# DBG-001.net
KiCad netlist of a schematic drawn in EAGLE
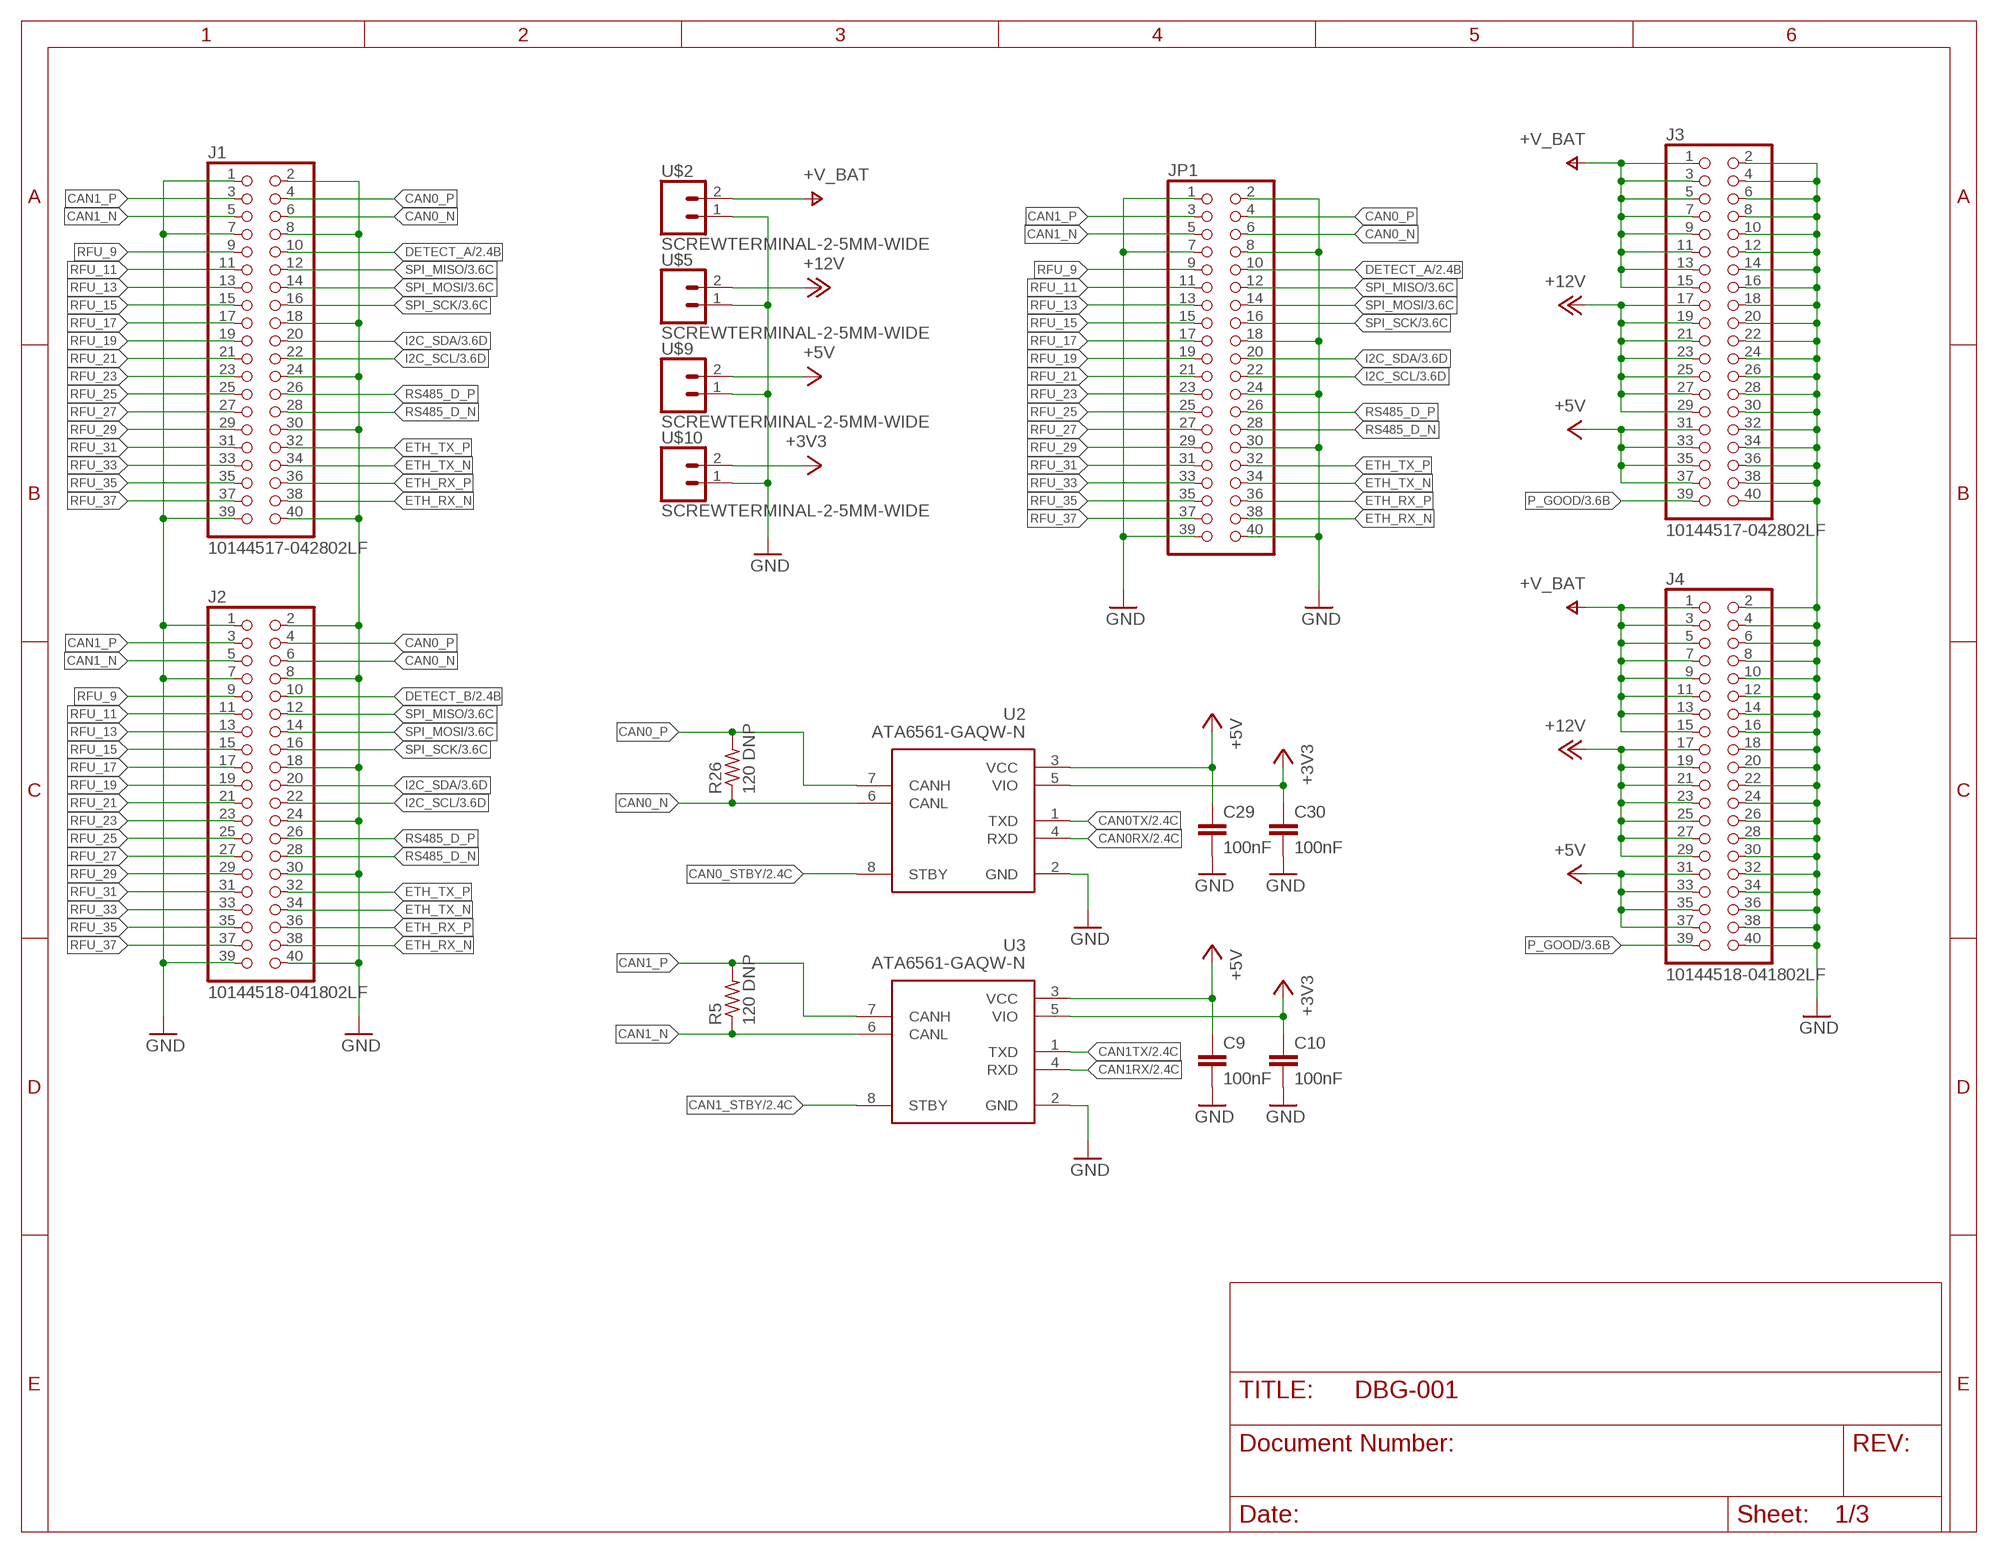
[diagram p0: schematic, sheet 1]
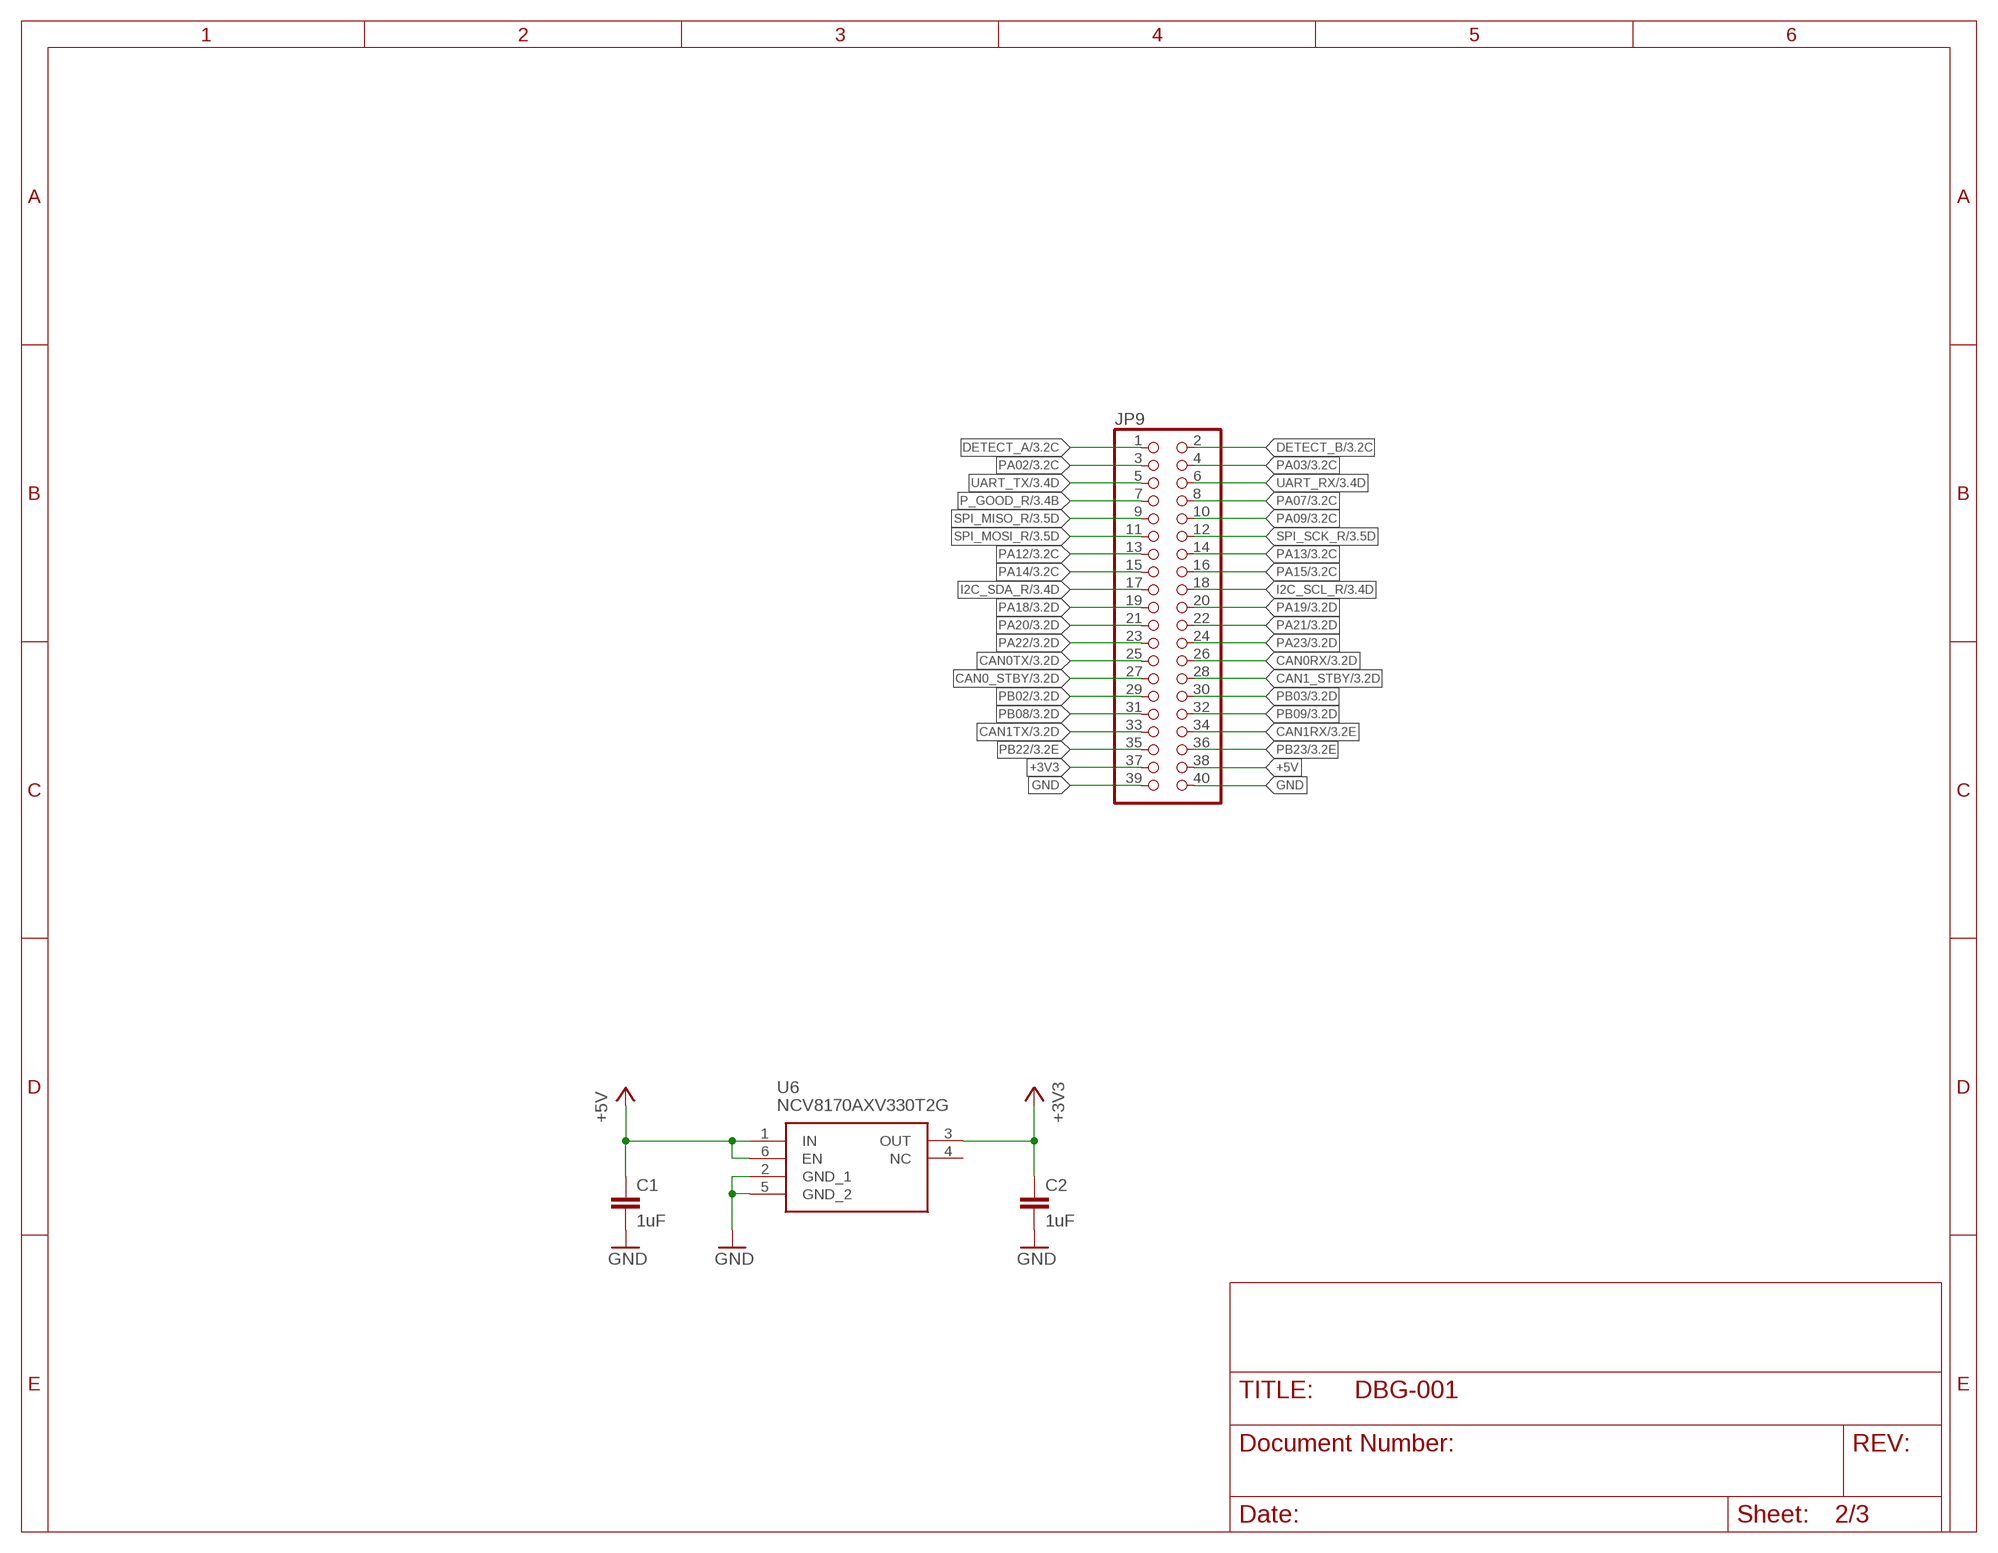
[diagram p1: schematic, sheet 2]
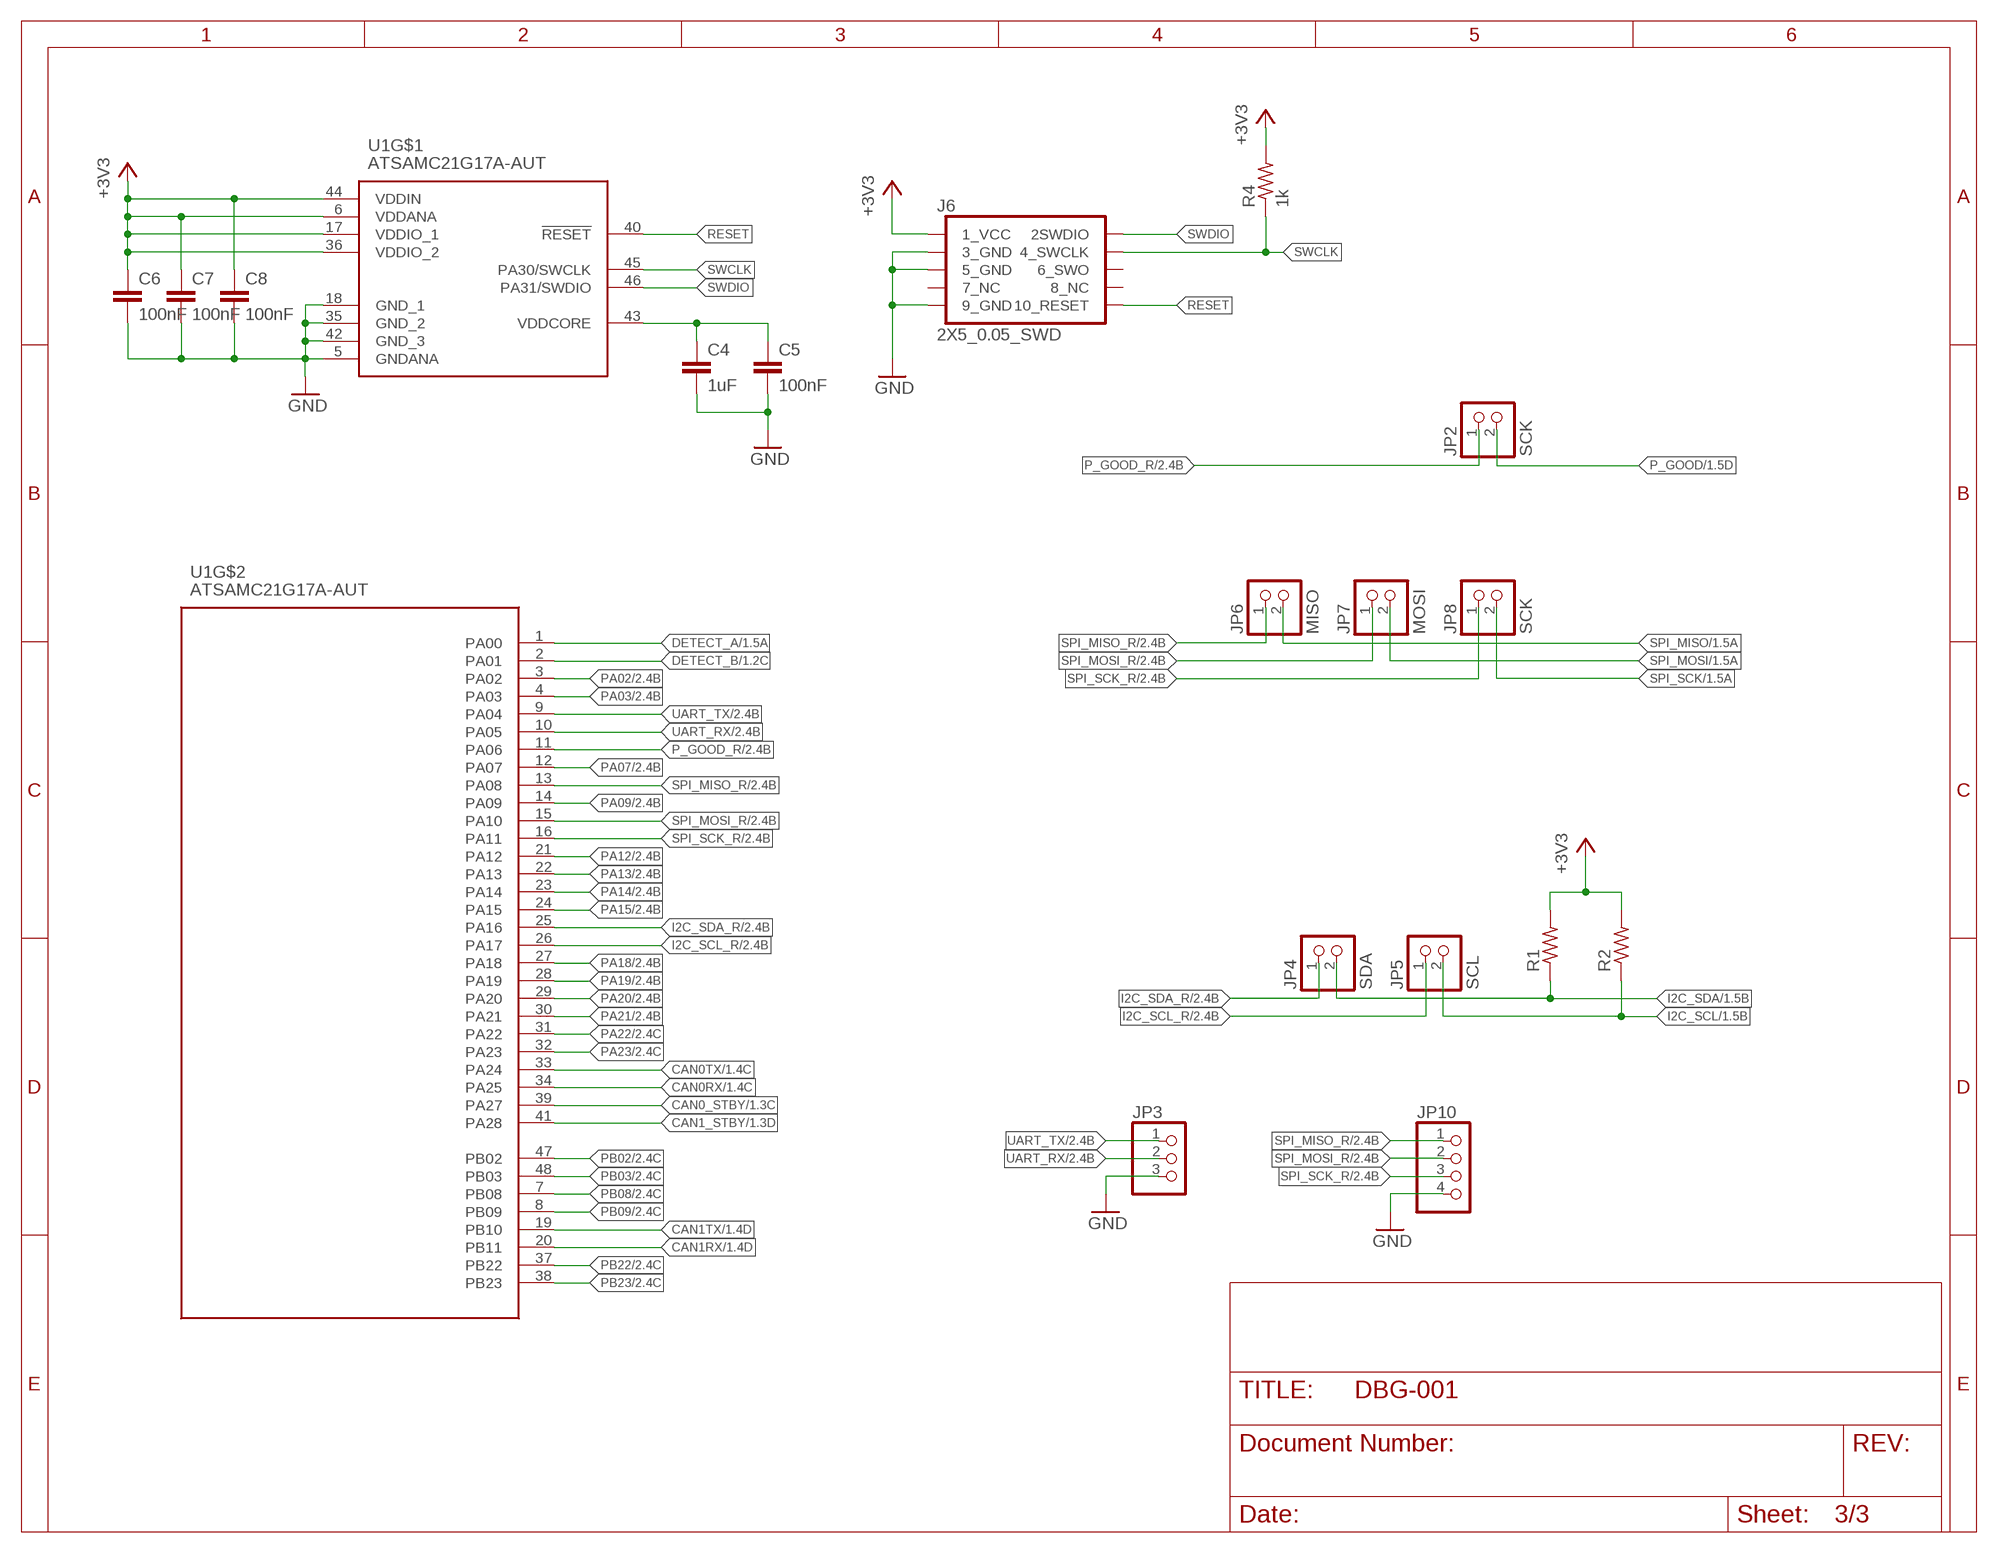
[diagram p2: schematic, sheet 3]

(export (version "E")
  (design (tool "Eeschema 10.0.6"))
  (components
    (comp (ref "C1")
      (value "1uF")
      (footprint "eagle-import:C0603")
      (libsource (lib "eagle-import") (part "C-EUC0603"))
    )
    (comp (ref "C2")
      (value "1uF")
      (footprint "eagle-import:C0603")
      (libsource (lib "eagle-import") (part "C-EUC0603"))
    )
    (comp (ref "JP9")
      (value "PINHD-2X20")
      (footprint "eagle-import:2X20")
      (libsource (lib "eagle-import") (part "PINHD-2X20"))
    )
    (comp (ref "U6")
      (value "NCV8170AXV330T2G")
      (footprint "eagle-import:SOTFL50P160X60-6N")
      (fields (field (name "MOUSER_PART_NUMBER") "863-NCV8170AXV330T2G"))
      (libsource (lib "eagle-import") (part "NCV8170AXV330T2G"))
    )
    (comp (ref "C9")
      (value "100nF")
      (footprint "eagle-import:C0402")
      (libsource (lib "eagle-import") (part "C-EUC0402"))
    )
    (comp (ref "C10")
      (value "100nF")
      (footprint "eagle-import:C0402")
      (libsource (lib "eagle-import") (part "C-EUC0402"))
    )
    (comp (ref "C29")
      (value "100nF")
      (footprint "eagle-import:C0402")
      (libsource (lib "eagle-import") (part "C-EUC0402"))
    )
    (comp (ref "C30")
      (value "100nF")
      (footprint "eagle-import:C0402")
      (libsource (lib "eagle-import") (part "C-EUC0402"))
    )
    (comp (ref "J1")
      (value "10144517-042802LF")
      (footprint "eagle-import:10144517-042802LF")
      (libsource (lib "eagle-import") (part "10144517-042802LF"))
    )
    (comp (ref "J2")
      (value "10144518-041802LF")
      (footprint "eagle-import:10144518-041802LF")
      (libsource (lib "eagle-import") (part "10144518-041802LF"))
    )
    (comp (ref "J3")
      (value "10144517-042802LF")
      (footprint "eagle-import:10144517-042802LF")
      (libsource (lib "eagle-import") (part "10144517-042802LF"))
    )
    (comp (ref "J4")
      (value "10144518-041802LF")
      (footprint "eagle-import:10144518-041802LF")
      (libsource (lib "eagle-import") (part "10144518-041802LF"))
    )
    (comp (ref "JP1")
      (value "PINHD-2X20")
      (footprint "eagle-import:2X20")
      (libsource (lib "eagle-import") (part "PINHD-2X20"))
    )
    (comp (ref "R5")
      (value "120 DNP")
      (footprint "eagle-import:R0402")
      (libsource (lib "eagle-import") (part "R-US_R0402"))
    )
    (comp (ref "R26")
      (value "120 DNP")
      (footprint "eagle-import:R0402")
      (libsource (lib "eagle-import") (part "R-US_R0402"))
    )
    (comp (ref "U$2")
      (value "SCREWTERMINAL-2-5MM-WIDE")
      (footprint "eagle-import:SCREWTERMINAL-5MM-2-WIDE")
      (libsource (lib "eagle-import") (part "SCREWTERMINAL-2-5MM-WIDE"))
    )
    (comp (ref "U$5")
      (value "SCREWTERMINAL-2-5MM-WIDE")
      (footprint "eagle-import:SCREWTERMINAL-5MM-2-WIDE")
      (libsource (lib "eagle-import") (part "SCREWTERMINAL-2-5MM-WIDE"))
    )
    (comp (ref "U$9")
      (value "SCREWTERMINAL-2-5MM-WIDE")
      (footprint "eagle-import:SCREWTERMINAL-5MM-2-WIDE")
      (libsource (lib "eagle-import") (part "SCREWTERMINAL-2-5MM-WIDE"))
    )
    (comp (ref "U$10")
      (value "SCREWTERMINAL-2-5MM-WIDE")
      (footprint "eagle-import:SCREWTERMINAL-5MM-2-WIDE")
      (libsource (lib "eagle-import") (part "SCREWTERMINAL-2-5MM-WIDE"))
    )
    (comp (ref "U2")
      (value "ATA6561-GAQW-N")
      (footprint "eagle-import:SOIC127P600X175-8N")
      (fields (field (name "MOUSER_PART_NUMBER") "579-ATA6561-GAQW-N"))
      (libsource (lib "eagle-import") (part "ATA6561-GAQW-N"))
    )
    (comp (ref "U3")
      (value "ATA6561-GAQW-N")
      (footprint "eagle-import:SOIC127P600X175-8N")
      (fields (field (name "MOUSER_PART_NUMBER") "579-ATA6561-GAQW-N"))
      (libsource (lib "eagle-import") (part "ATA6561-GAQW-N"))
    )
    (comp (ref "C4")
      (value "1uF")
      (footprint "eagle-import:C0805")
      (libsource (lib "eagle-import") (part "C-EUC0805"))
    )
    (comp (ref "C5")
      (value "100nF")
      (footprint "eagle-import:C0805")
      (libsource (lib "eagle-import") (part "C-EUC0805"))
    )
    (comp (ref "C6")
      (value "100nF")
      (footprint "eagle-import:C0805")
      (libsource (lib "eagle-import") (part "C-EUC0805"))
    )
    (comp (ref "C7")
      (value "100nF")
      (footprint "eagle-import:C0805")
      (libsource (lib "eagle-import") (part "C-EUC0805"))
    )
    (comp (ref "C8")
      (value "100nF")
      (footprint "eagle-import:C0805")
      (libsource (lib "eagle-import") (part "C-EUC0805"))
    )
    (comp (ref "J6")
      (value "2X5_0.05_SWD")
      (footprint "eagle-import:2X5_RIGHT")
      (libsource (lib "eagle-import") (part "2X5_0.05_SWD"))
    )
    (comp (ref "JP2")
      (value "SCK")
      (footprint "eagle-import:1X02")
      (libsource (lib "eagle-import") (part "PINHD-1X2"))
    )
    (comp (ref "JP3")
      (value "PINHD-1X3")
      (footprint "eagle-import:1X03")
      (libsource (lib "eagle-import") (part "PINHD-1X3"))
    )
    (comp (ref "JP4")
      (value "SDA")
      (footprint "eagle-import:1X02")
      (libsource (lib "eagle-import") (part "PINHD-1X2"))
    )
    (comp (ref "JP5")
      (value "SCL")
      (footprint "eagle-import:1X02")
      (libsource (lib "eagle-import") (part "PINHD-1X2"))
    )
    (comp (ref "JP6")
      (value "MISO")
      (footprint "eagle-import:1X02")
      (libsource (lib "eagle-import") (part "PINHD-1X2"))
    )
    (comp (ref "JP7")
      (value "MOSI")
      (footprint "eagle-import:1X02")
      (libsource (lib "eagle-import") (part "PINHD-1X2"))
    )
    (comp (ref "JP8")
      (value "SCK")
      (footprint "eagle-import:1X02")
      (libsource (lib "eagle-import") (part "PINHD-1X2"))
    )
    (comp (ref "JP10")
      (value "PINHD-1X4")
      (footprint "eagle-import:1X04")
      (libsource (lib "eagle-import") (part "PINHD-1X4"))
    )
    (comp (ref "R1")
      (value "R-US_R0805")
      (footprint "eagle-import:R0805")
      (libsource (lib "eagle-import") (part "R-US_R0805"))
    )
    (comp (ref "R2")
      (value "R-US_R0805")
      (footprint "eagle-import:R0805")
      (libsource (lib "eagle-import") (part "R-US_R0805"))
    )
    (comp (ref "R4")
      (value "1k")
      (footprint "eagle-import:R0402")
      (libsource (lib "eagle-import") (part "R-US_R0402"))
    )
    (comp (ref "U1")
      (value "ATSAMC21G17A-AUT")
      (footprint "eagle-import:QFP50P900X900X120-48N")
      (libsource (lib "eagle-import") (part "ATSAMC21G17A-AUT"))
    )
  )
  (nets
    (net (code "1") (name "+3V3") (class "Default")
      (node (ref "C10") (pin "1") (pinfunction "1_1") (pintype "passive"))
      (node (ref "C2") (pin "1") (pinfunction "1_1") (pintype "passive"))
      (node (ref "C30") (pin "1") (pinfunction "1_1") (pintype "passive"))
      (node (ref "C6") (pin "1") (pinfunction "1_1") (pintype "passive"))
      (node (ref "C7") (pin "1") (pinfunction "1_1") (pintype "passive"))
      (node (ref "C8") (pin "1") (pinfunction "1_1") (pintype "passive"))
      (node (ref "J6") (pin "1") (pinfunction "1_VCC_1") (pintype "passive"))
      (node (ref "JP9") (pin "37") (pinfunction "37_37") (pintype "passive"))
      (node (ref "R1") (pin "2") (pinfunction "2_2") (pintype "passive"))
      (node (ref "R2") (pin "2") (pinfunction "2_2") (pintype "passive"))
      (node (ref "R4") (pin "2") (pinfunction "2_2") (pintype "passive"))
      (node (ref "U$10") (pin "2") (pinfunction "2_2") (pintype "passive"))
      (node (ref "U1") (pin "17") (pinfunction "VDDIO_1_17") (pintype "bidirectional"))
      (node (ref "U1") (pin "36") (pinfunction "VDDIO_2_36") (pintype "bidirectional"))
      (node (ref "U1") (pin "44") (pinfunction "VDDIN_44") (pintype "power_in"))
      (node (ref "U1") (pin "6") (pinfunction "VDDANA_6") (pintype "power_in"))
      (node (ref "U2") (pin "5") (pinfunction "VIO_5") (pintype "bidirectional"))
      (node (ref "U3") (pin "5") (pinfunction "VIO_5") (pintype "bidirectional"))
      (node (ref "U6") (pin "3") (pinfunction "OUT_3") (pintype "bidirectional"))
    )
    (net (code "2") (name "+5V") (class "Default")
      (node (ref "C1") (pin "1") (pinfunction "1_1") (pintype "passive"))
      (node (ref "C29") (pin "1") (pinfunction "1_1") (pintype "passive"))
      (node (ref "C9") (pin "1") (pinfunction "1_1") (pintype "passive"))
      (node (ref "J3") (pin "31") (pinfunction "31_31") (pintype "passive"))
      (node (ref "J3") (pin "33") (pinfunction "33_33") (pintype "passive"))
      (node (ref "J3") (pin "35") (pinfunction "35_35") (pintype "passive"))
      (node (ref "J3") (pin "37") (pinfunction "37_37") (pintype "passive"))
      (node (ref "J4") (pin "31") (pinfunction "31_31") (pintype "passive"))
      (node (ref "J4") (pin "33") (pinfunction "33_33") (pintype "passive"))
      (node (ref "J4") (pin "35") (pinfunction "35_35") (pintype "passive"))
      (node (ref "J4") (pin "37") (pinfunction "37_37") (pintype "passive"))
      (node (ref "JP9") (pin "38") (pinfunction "38_38") (pintype "passive"))
      (node (ref "U$9") (pin "2") (pinfunction "2_2") (pintype "passive"))
      (node (ref "U2") (pin "3") (pinfunction "VCC_3") (pintype "bidirectional"))
      (node (ref "U3") (pin "3") (pinfunction "VCC_3") (pintype "bidirectional"))
      (node (ref "U6") (pin "1") (pinfunction "IN_1") (pintype "bidirectional"))
      (node (ref "U6") (pin "6") (pinfunction "EN_6") (pintype "bidirectional"))
    )
    (net (code "3") (name "+12V") (class "Default")
      (node (ref "J3") (pin "17") (pinfunction "17_17") (pintype "passive"))
      (node (ref "J3") (pin "19") (pinfunction "19_19") (pintype "passive"))
      (node (ref "J3") (pin "21") (pinfunction "21_21") (pintype "passive"))
      (node (ref "J3") (pin "23") (pinfunction "23_23") (pintype "passive"))
      (node (ref "J3") (pin "25") (pinfunction "25_25") (pintype "passive"))
      (node (ref "J3") (pin "27") (pinfunction "27_27") (pintype "passive"))
      (node (ref "J3") (pin "29") (pinfunction "29_29") (pintype "passive"))
      (node (ref "J4") (pin "17") (pinfunction "17_17") (pintype "passive"))
      (node (ref "J4") (pin "19") (pinfunction "19_19") (pintype "passive"))
      (node (ref "J4") (pin "21") (pinfunction "21_21") (pintype "passive"))
      (node (ref "J4") (pin "23") (pinfunction "23_23") (pintype "passive"))
      (node (ref "J4") (pin "25") (pinfunction "25_25") (pintype "passive"))
      (node (ref "J4") (pin "27") (pinfunction "27_27") (pintype "passive"))
      (node (ref "J4") (pin "29") (pinfunction "29_29") (pintype "passive"))
      (node (ref "U$5") (pin "2") (pinfunction "2_2") (pintype "passive"))
    )
    (net (code "4") (name "+V_BAT") (class "Default")
      (node (ref "J3") (pin "1") (pinfunction "1_1") (pintype "passive"))
      (node (ref "J3") (pin "11") (pinfunction "11_11") (pintype "passive"))
      (node (ref "J3") (pin "13") (pinfunction "13_13") (pintype "passive"))
      (node (ref "J3") (pin "15") (pinfunction "15_15") (pintype "passive"))
      (node (ref "J3") (pin "3") (pinfunction "3_3") (pintype "passive"))
      (node (ref "J3") (pin "5") (pinfunction "5_5") (pintype "passive"))
      (node (ref "J3") (pin "7") (pinfunction "7_7") (pintype "passive"))
      (node (ref "J3") (pin "9") (pinfunction "9_9") (pintype "passive"))
      (node (ref "J4") (pin "1") (pinfunction "1_1") (pintype "passive"))
      (node (ref "J4") (pin "11") (pinfunction "11_11") (pintype "passive"))
      (node (ref "J4") (pin "13") (pinfunction "13_13") (pintype "passive"))
      (node (ref "J4") (pin "15") (pinfunction "15_15") (pintype "passive"))
      (node (ref "J4") (pin "3") (pinfunction "3_3") (pintype "passive"))
      (node (ref "J4") (pin "5") (pinfunction "5_5") (pintype "passive"))
      (node (ref "J4") (pin "7") (pinfunction "7_7") (pintype "passive"))
      (node (ref "J4") (pin "9") (pinfunction "9_9") (pintype "passive"))
      (node (ref "U$2") (pin "2") (pinfunction "2_2") (pintype "passive"))
    )
    (net (code "5") (name "CAN0RX") (class "Default")
      (node (ref "JP9") (pin "26") (pinfunction "26_26") (pintype "passive"))
      (node (ref "U1") (pin "34") (pinfunction "PA25_34") (pintype "bidirectional"))
      (node (ref "U2") (pin "4") (pinfunction "RXD_4") (pintype "bidirectional"))
    )
    (net (code "6") (name "CAN0TX") (class "Default")
      (node (ref "JP9") (pin "25") (pinfunction "25_25") (pintype "passive"))
      (node (ref "U1") (pin "33") (pinfunction "PA24_33") (pintype "bidirectional"))
      (node (ref "U2") (pin "1") (pinfunction "TXD_1") (pintype "bidirectional"))
    )
    (net (code "7") (name "CAN0_N") (class "Default")
      (node (ref "J1") (pin "6") (pinfunction "6_6") (pintype "passive"))
      (node (ref "J2") (pin "6") (pinfunction "6_6") (pintype "passive"))
      (node (ref "JP1") (pin "6") (pinfunction "6_6") (pintype "passive"))
      (node (ref "R26") (pin "1") (pinfunction "1_1") (pintype "passive"))
      (node (ref "U2") (pin "6") (pinfunction "CANL_6") (pintype "bidirectional"))
    )
    (net (code "8") (name "CAN0_P") (class "Default")
      (node (ref "J1") (pin "4") (pinfunction "4_4") (pintype "passive"))
      (node (ref "J2") (pin "4") (pinfunction "4_4") (pintype "passive"))
      (node (ref "JP1") (pin "4") (pinfunction "4_4") (pintype "passive"))
      (node (ref "R26") (pin "2") (pinfunction "2_2") (pintype "passive"))
      (node (ref "U2") (pin "7") (pinfunction "CANH_7") (pintype "bidirectional"))
    )
    (net (code "9") (name "CAN0_STBY") (class "Default")
      (node (ref "JP9") (pin "27") (pinfunction "27_27") (pintype "passive"))
      (node (ref "U1") (pin "39") (pinfunction "PA27_39") (pintype "bidirectional"))
      (node (ref "U2") (pin "8") (pinfunction "STBY_8") (pintype "bidirectional"))
    )
    (net (code "10") (name "CAN1RX") (class "Default")
      (node (ref "JP9") (pin "34") (pinfunction "34_34") (pintype "passive"))
      (node (ref "U1") (pin "20") (pinfunction "PB11_20") (pintype "bidirectional"))
      (node (ref "U3") (pin "4") (pinfunction "RXD_4") (pintype "bidirectional"))
    )
    (net (code "11") (name "CAN1TX") (class "Default")
      (node (ref "JP9") (pin "33") (pinfunction "33_33") (pintype "passive"))
      (node (ref "U1") (pin "19") (pinfunction "PB10_19") (pintype "bidirectional"))
      (node (ref "U3") (pin "1") (pinfunction "TXD_1") (pintype "bidirectional"))
    )
    (net (code "12") (name "CAN1_N") (class "Default")
      (node (ref "J1") (pin "5") (pinfunction "5_5") (pintype "passive"))
      (node (ref "J2") (pin "5") (pinfunction "5_5") (pintype "passive"))
      (node (ref "JP1") (pin "5") (pinfunction "5_5") (pintype "passive"))
      (node (ref "R5") (pin "1") (pinfunction "1_1") (pintype "passive"))
      (node (ref "U3") (pin "6") (pinfunction "CANL_6") (pintype "bidirectional"))
    )
    (net (code "13") (name "CAN1_P") (class "Default")
      (node (ref "J1") (pin "3") (pinfunction "3_3") (pintype "passive"))
      (node (ref "J2") (pin "3") (pinfunction "3_3") (pintype "passive"))
      (node (ref "JP1") (pin "3") (pinfunction "3_3") (pintype "passive"))
      (node (ref "R5") (pin "2") (pinfunction "2_2") (pintype "passive"))
      (node (ref "U3") (pin "7") (pinfunction "CANH_7") (pintype "bidirectional"))
    )
    (net (code "14") (name "CAN1_STBY") (class "Default")
      (node (ref "JP9") (pin "28") (pinfunction "28_28") (pintype "passive"))
      (node (ref "U1") (pin "41") (pinfunction "PA28_41") (pintype "bidirectional"))
      (node (ref "U3") (pin "8") (pinfunction "STBY_8") (pintype "bidirectional"))
    )
    (net (code "15") (name "DETECT_A") (class "Default")
      (node (ref "J1") (pin "10") (pinfunction "10_10") (pintype "passive"))
      (node (ref "JP1") (pin "10") (pinfunction "10_10") (pintype "passive"))
      (node (ref "JP9") (pin "1") (pinfunction "1_1") (pintype "passive"))
      (node (ref "U1") (pin "1") (pinfunction "PA00_1") (pintype "bidirectional"))
    )
    (net (code "16") (name "DETECT_B") (class "Default")
      (node (ref "J2") (pin "10") (pinfunction "10_10") (pintype "passive"))
      (node (ref "JP9") (pin "2") (pinfunction "2_2") (pintype "passive"))
      (node (ref "U1") (pin "2") (pinfunction "PA01_2") (pintype "bidirectional"))
    )
    (net (code "17") (name "ETH_RX_N") (class "Default")
      (node (ref "J1") (pin "38") (pinfunction "38_38") (pintype "passive"))
      (node (ref "J2") (pin "38") (pinfunction "38_38") (pintype "passive"))
      (node (ref "JP1") (pin "38") (pinfunction "38_38") (pintype "passive"))
    )
    (net (code "18") (name "ETH_RX_P") (class "Default")
      (node (ref "J1") (pin "36") (pinfunction "36_36") (pintype "passive"))
      (node (ref "J2") (pin "36") (pinfunction "36_36") (pintype "passive"))
      (node (ref "JP1") (pin "36") (pinfunction "36_36") (pintype "passive"))
    )
    (net (code "19") (name "ETH_TX_N") (class "Default")
      (node (ref "J1") (pin "34") (pinfunction "34_34") (pintype "passive"))
      (node (ref "J2") (pin "34") (pinfunction "34_34") (pintype "passive"))
      (node (ref "JP1") (pin "34") (pinfunction "34_34") (pintype "passive"))
    )
    (net (code "20") (name "ETH_TX_P") (class "Default")
      (node (ref "J1") (pin "32") (pinfunction "32_32") (pintype "passive"))
      (node (ref "J2") (pin "32") (pinfunction "32_32") (pintype "passive"))
      (node (ref "JP1") (pin "32") (pinfunction "32_32") (pintype "passive"))
    )
    (net (code "21") (name "GND") (class "Default")
      (node (ref "C1") (pin "2") (pinfunction "2_2") (pintype "passive"))
      (node (ref "C10") (pin "2") (pinfunction "2_2") (pintype "passive"))
      (node (ref "C2") (pin "2") (pinfunction "2_2") (pintype "passive"))
      (node (ref "C29") (pin "2") (pinfunction "2_2") (pintype "passive"))
      (node (ref "C30") (pin "2") (pinfunction "2_2") (pintype "passive"))
      (node (ref "C4") (pin "2") (pinfunction "2_2") (pintype "passive"))
      (node (ref "C5") (pin "2") (pinfunction "2_2") (pintype "passive"))
      (node (ref "C6") (pin "2") (pinfunction "2_2") (pintype "passive"))
      (node (ref "C7") (pin "2") (pinfunction "2_2") (pintype "passive"))
      (node (ref "C8") (pin "2") (pinfunction "2_2") (pintype "passive"))
      (node (ref "C9") (pin "2") (pinfunction "2_2") (pintype "passive"))
      (node (ref "J1") (pin "1") (pinfunction "1_1") (pintype "passive"))
      (node (ref "J1") (pin "18") (pinfunction "18_18") (pintype "passive"))
      (node (ref "J1") (pin "2") (pinfunction "2_2") (pintype "passive"))
      (node (ref "J1") (pin "24") (pinfunction "24_24") (pintype "passive"))
      (node (ref "J1") (pin "30") (pinfunction "30_30") (pintype "passive"))
      (node (ref "J1") (pin "39") (pinfunction "39_39") (pintype "passive"))
      (node (ref "J1") (pin "40") (pinfunction "40_40") (pintype "passive"))
      (node (ref "J1") (pin "7") (pinfunction "7_7") (pintype "passive"))
      (node (ref "J1") (pin "8") (pinfunction "8_8") (pintype "passive"))
      (node (ref "J2") (pin "1") (pinfunction "1_1") (pintype "passive"))
      (node (ref "J2") (pin "18") (pinfunction "18_18") (pintype "passive"))
      (node (ref "J2") (pin "2") (pinfunction "2_2") (pintype "passive"))
      (node (ref "J2") (pin "24") (pinfunction "24_24") (pintype "passive"))
      (node (ref "J2") (pin "30") (pinfunction "30_30") (pintype "passive"))
      (node (ref "J2") (pin "39") (pinfunction "39_39") (pintype "passive"))
      (node (ref "J2") (pin "40") (pinfunction "40_40") (pintype "passive"))
      (node (ref "J2") (pin "7") (pinfunction "7_7") (pintype "passive"))
      (node (ref "J2") (pin "8") (pinfunction "8_8") (pintype "passive"))
      (node (ref "J3") (pin "10") (pinfunction "10_10") (pintype "passive"))
      (node (ref "J3") (pin "12") (pinfunction "12_12") (pintype "passive"))
      (node (ref "J3") (pin "14") (pinfunction "14_14") (pintype "passive"))
      (node (ref "J3") (pin "16") (pinfunction "16_16") (pintype "passive"))
      (node (ref "J3") (pin "18") (pinfunction "18_18") (pintype "passive"))
      (node (ref "J3") (pin "2") (pinfunction "2_2") (pintype "passive"))
      (node (ref "J3") (pin "20") (pinfunction "20_20") (pintype "passive"))
      (node (ref "J3") (pin "22") (pinfunction "22_22") (pintype "passive"))
      (node (ref "J3") (pin "24") (pinfunction "24_24") (pintype "passive"))
      (node (ref "J3") (pin "26") (pinfunction "26_26") (pintype "passive"))
      (node (ref "J3") (pin "28") (pinfunction "28_28") (pintype "passive"))
      (node (ref "J3") (pin "30") (pinfunction "30_30") (pintype "passive"))
      (node (ref "J3") (pin "32") (pinfunction "32_32") (pintype "passive"))
      (node (ref "J3") (pin "34") (pinfunction "34_34") (pintype "passive"))
      (node (ref "J3") (pin "36") (pinfunction "36_36") (pintype "passive"))
      (node (ref "J3") (pin "38") (pinfunction "38_38") (pintype "passive"))
      (node (ref "J3") (pin "4") (pinfunction "4_4") (pintype "passive"))
      (node (ref "J3") (pin "40") (pinfunction "40_40") (pintype "passive"))
      (node (ref "J3") (pin "6") (pinfunction "6_6") (pintype "passive"))
      (node (ref "J3") (pin "8") (pinfunction "8_8") (pintype "passive"))
      (node (ref "J4") (pin "10") (pinfunction "10_10") (pintype "passive"))
      (node (ref "J4") (pin "12") (pinfunction "12_12") (pintype "passive"))
      (node (ref "J4") (pin "14") (pinfunction "14_14") (pintype "passive"))
      (node (ref "J4") (pin "16") (pinfunction "16_16") (pintype "passive"))
      (node (ref "J4") (pin "18") (pinfunction "18_18") (pintype "passive"))
      (node (ref "J4") (pin "2") (pinfunction "2_2") (pintype "passive"))
      (node (ref "J4") (pin "20") (pinfunction "20_20") (pintype "passive"))
      (node (ref "J4") (pin "22") (pinfunction "22_22") (pintype "passive"))
      (node (ref "J4") (pin "24") (pinfunction "24_24") (pintype "passive"))
      (node (ref "J4") (pin "26") (pinfunction "26_26") (pintype "passive"))
      (node (ref "J4") (pin "28") (pinfunction "28_28") (pintype "passive"))
      (node (ref "J4") (pin "30") (pinfunction "30_30") (pintype "passive"))
      (node (ref "J4") (pin "32") (pinfunction "32_32") (pintype "passive"))
      (node (ref "J4") (pin "34") (pinfunction "34_34") (pintype "passive"))
      (node (ref "J4") (pin "36") (pinfunction "36_36") (pintype "passive"))
      (node (ref "J4") (pin "38") (pinfunction "38_38") (pintype "passive"))
      (node (ref "J4") (pin "4") (pinfunction "4_4") (pintype "passive"))
      (node (ref "J4") (pin "40") (pinfunction "40_40") (pintype "passive"))
      (node (ref "J4") (pin "6") (pinfunction "6_6") (pintype "passive"))
      (node (ref "J4") (pin "8") (pinfunction "8_8") (pintype "passive"))
      (node (ref "J6") (pin "3") (pinfunction "3_GND_3") (pintype "passive"))
      (node (ref "J6") (pin "5") (pinfunction "5_GND_5") (pintype "passive"))
      (node (ref "J6") (pin "9") (pinfunction "9_GND_9") (pintype "passive"))
      (node (ref "JP1") (pin "1") (pinfunction "1_1") (pintype "passive"))
      (node (ref "JP1") (pin "18") (pinfunction "18_18") (pintype "passive"))
      (node (ref "JP1") (pin "2") (pinfunction "2_2") (pintype "passive"))
      (node (ref "JP1") (pin "24") (pinfunction "24_24") (pintype "passive"))
      (node (ref "JP1") (pin "30") (pinfunction "30_30") (pintype "passive"))
      (node (ref "JP1") (pin "39") (pinfunction "39_39") (pintype "passive"))
      (node (ref "JP1") (pin "40") (pinfunction "40_40") (pintype "passive"))
      (node (ref "JP1") (pin "7") (pinfunction "7_7") (pintype "passive"))
      (node (ref "JP1") (pin "8") (pinfunction "8_8") (pintype "passive"))
      (node (ref "JP10") (pin "4") (pinfunction "4_4") (pintype "passive"))
      (node (ref "JP3") (pin "3") (pinfunction "3_3") (pintype "passive"))
      (node (ref "JP9") (pin "39") (pinfunction "39_39") (pintype "passive"))
      (node (ref "JP9") (pin "40") (pinfunction "40_40") (pintype "passive"))
      (node (ref "U$10") (pin "1") (pinfunction "1_1") (pintype "passive"))
      (node (ref "U$2") (pin "1") (pinfunction "1_1") (pintype "passive"))
      (node (ref "U$5") (pin "1") (pinfunction "1_1") (pintype "passive"))
      (node (ref "U$9") (pin "1") (pinfunction "1_1") (pintype "passive"))
      (node (ref "U1") (pin "18") (pinfunction "GND_1_18") (pintype "power_in"))
      (node (ref "U1") (pin "35") (pinfunction "GND_2_35") (pintype "power_in"))
      (node (ref "U1") (pin "42") (pinfunction "GND_3_42") (pintype "bidirectional"))
      (node (ref "U1") (pin "5") (pinfunction "GNDANA_5") (pintype "bidirectional"))
      (node (ref "U2") (pin "2") (pinfunction "GND_2") (pintype "bidirectional"))
      (node (ref "U3") (pin "2") (pinfunction "GND_2") (pintype "bidirectional"))
      (node (ref "U6") (pin "2") (pinfunction "GND_1_2") (pintype "bidirectional"))
      (node (ref "U6") (pin "5") (pinfunction "GND_2_5") (pintype "bidirectional"))
    )
    (net (code "22") (name "I2C_SCL") (class "Default")
      (node (ref "J1") (pin "22") (pinfunction "22_22") (pintype "passive"))
      (node (ref "J2") (pin "22") (pinfunction "22_22") (pintype "passive"))
      (node (ref "JP1") (pin "22") (pinfunction "22_22") (pintype "passive"))
      (node (ref "JP5") (pin "2") (pinfunction "2_2") (pintype "passive"))
      (node (ref "R2") (pin "1") (pinfunction "1_1") (pintype "passive"))
    )
    (net (code "23") (name "I2C_SCL_R") (class "Default")
      (node (ref "JP5") (pin "1") (pinfunction "1_1") (pintype "passive"))
      (node (ref "JP9") (pin "18") (pinfunction "18_18") (pintype "passive"))
      (node (ref "U1") (pin "26") (pinfunction "PA17_26") (pintype "bidirectional"))
    )
    (net (code "24") (name "I2C_SDA") (class "Default")
      (node (ref "J1") (pin "20") (pinfunction "20_20") (pintype "passive"))
      (node (ref "J2") (pin "20") (pinfunction "20_20") (pintype "passive"))
      (node (ref "JP1") (pin "20") (pinfunction "20_20") (pintype "passive"))
      (node (ref "JP4") (pin "2") (pinfunction "2_2") (pintype "passive"))
      (node (ref "R1") (pin "1") (pinfunction "1_1") (pintype "passive"))
    )
    (net (code "25") (name "I2C_SDA_R") (class "Default")
      (node (ref "JP4") (pin "1") (pinfunction "1_1") (pintype "passive"))
      (node (ref "JP9") (pin "17") (pinfunction "17_17") (pintype "passive"))
      (node (ref "U1") (pin "25") (pinfunction "PA16_25") (pintype "bidirectional"))
    )
    (net (code "26") (name "Net-(U1A-VDDCORE)") (class "Default")
      (node (ref "C4") (pin "1") (pinfunction "1_1") (pintype "passive"))
      (node (ref "C5") (pin "1") (pinfunction "1_1") (pintype "passive"))
      (node (ref "U1") (pin "43") (pinfunction "VDDCORE_43") (pintype "power_in"))
    )
    (net (code "27") (name "PA02") (class "Default")
      (node (ref "JP9") (pin "3") (pinfunction "3_3") (pintype "passive"))
      (node (ref "U1") (pin "3") (pinfunction "PA02_3") (pintype "bidirectional"))
    )
    (net (code "28") (name "PA03") (class "Default")
      (node (ref "JP9") (pin "4") (pinfunction "4_4") (pintype "passive"))
      (node (ref "U1") (pin "4") (pinfunction "PA03_4") (pintype "bidirectional"))
    )
    (net (code "29") (name "PA07") (class "Default")
      (node (ref "JP9") (pin "8") (pinfunction "8_8") (pintype "passive"))
      (node (ref "U1") (pin "12") (pinfunction "PA07_12") (pintype "bidirectional"))
    )
    (net (code "30") (name "PA09") (class "Default")
      (node (ref "JP9") (pin "10") (pinfunction "10_10") (pintype "passive"))
      (node (ref "U1") (pin "14") (pinfunction "PA09_14") (pintype "bidirectional"))
    )
    (net (code "31") (name "PA12") (class "Default")
      (node (ref "JP9") (pin "13") (pinfunction "13_13") (pintype "passive"))
      (node (ref "U1") (pin "21") (pinfunction "PA12_21") (pintype "bidirectional"))
    )
    (net (code "32") (name "PA13") (class "Default")
      (node (ref "JP9") (pin "14") (pinfunction "14_14") (pintype "passive"))
      (node (ref "U1") (pin "22") (pinfunction "PA13_22") (pintype "bidirectional"))
    )
    (net (code "33") (name "PA14") (class "Default")
      (node (ref "JP9") (pin "15") (pinfunction "15_15") (pintype "passive"))
      (node (ref "U1") (pin "23") (pinfunction "PA14_23") (pintype "bidirectional"))
    )
    (net (code "34") (name "PA15") (class "Default")
      (node (ref "JP9") (pin "16") (pinfunction "16_16") (pintype "passive"))
      (node (ref "U1") (pin "24") (pinfunction "PA15_24") (pintype "bidirectional"))
    )
    (net (code "35") (name "PA18") (class "Default")
      (node (ref "JP9") (pin "19") (pinfunction "19_19") (pintype "passive"))
      (node (ref "U1") (pin "27") (pinfunction "PA18_27") (pintype "bidirectional"))
    )
    (net (code "36") (name "PA19") (class "Default")
      (node (ref "JP9") (pin "20") (pinfunction "20_20") (pintype "passive"))
      (node (ref "U1") (pin "28") (pinfunction "PA19_28") (pintype "bidirectional"))
    )
    (net (code "37") (name "PA20") (class "Default")
      (node (ref "JP9") (pin "21") (pinfunction "21_21") (pintype "passive"))
      (node (ref "U1") (pin "29") (pinfunction "PA20_29") (pintype "bidirectional"))
    )
    (net (code "38") (name "PA21") (class "Default")
      (node (ref "JP9") (pin "22") (pinfunction "22_22") (pintype "passive"))
      (node (ref "U1") (pin "30") (pinfunction "PA21_30") (pintype "bidirectional"))
    )
    (net (code "39") (name "PA22") (class "Default")
      (node (ref "JP9") (pin "23") (pinfunction "23_23") (pintype "passive"))
      (node (ref "U1") (pin "31") (pinfunction "PA22_31") (pintype "bidirectional"))
    )
    (net (code "40") (name "PA23") (class "Default")
      (node (ref "JP9") (pin "24") (pinfunction "24_24") (pintype "passive"))
      (node (ref "U1") (pin "32") (pinfunction "PA23_32") (pintype "bidirectional"))
    )
    (net (code "41") (name "PB02") (class "Default")
      (node (ref "JP9") (pin "29") (pinfunction "29_29") (pintype "passive"))
      (node (ref "U1") (pin "47") (pinfunction "PB02_47") (pintype "bidirectional"))
    )
    (net (code "42") (name "PB03") (class "Default")
      (node (ref "JP9") (pin "30") (pinfunction "30_30") (pintype "passive"))
      (node (ref "U1") (pin "48") (pinfunction "PB03_48") (pintype "bidirectional"))
    )
    (net (code "43") (name "PB08") (class "Default")
      (node (ref "JP9") (pin "31") (pinfunction "31_31") (pintype "passive"))
      (node (ref "U1") (pin "7") (pinfunction "PB08_7") (pintype "bidirectional"))
    )
    (net (code "44") (name "PB09") (class "Default")
      (node (ref "JP9") (pin "32") (pinfunction "32_32") (pintype "passive"))
      (node (ref "U1") (pin "8") (pinfunction "PB09_8") (pintype "bidirectional"))
    )
    (net (code "45") (name "PB22") (class "Default")
      (node (ref "JP9") (pin "35") (pinfunction "35_35") (pintype "passive"))
      (node (ref "U1") (pin "37") (pinfunction "PB22_37") (pintype "bidirectional"))
    )
    (net (code "46") (name "PB23") (class "Default")
      (node (ref "JP9") (pin "36") (pinfunction "36_36") (pintype "passive"))
      (node (ref "U1") (pin "38") (pinfunction "PB23_38") (pintype "bidirectional"))
    )
    (net (code "47") (name "P_GOOD") (class "Default")
      (node (ref "J3") (pin "39") (pinfunction "39_39") (pintype "passive"))
      (node (ref "J4") (pin "39") (pinfunction "39_39") (pintype "passive"))
      (node (ref "JP2") (pin "2") (pinfunction "2_2") (pintype "passive"))
    )
    (net (code "48") (name "P_GOOD_R") (class "Default")
      (node (ref "JP2") (pin "1") (pinfunction "1_1") (pintype "passive"))
      (node (ref "JP9") (pin "7") (pinfunction "7_7") (pintype "passive"))
      (node (ref "U1") (pin "11") (pinfunction "PA06_11") (pintype "bidirectional"))
    )
    (net (code "49") (name "RESET") (class "Default")
      (node (ref "J6") (pin "10") (pinfunction "10_RESET_10") (pintype "passive"))
      (node (ref "U1") (pin "40") (pinfunction "~{RESET}_40") (pintype "input"))
    )
    (net (code "50") (name "RFU_9") (class "Default")
      (node (ref "J1") (pin "9") (pinfunction "9_9") (pintype "passive"))
      (node (ref "J2") (pin "9") (pinfunction "9_9") (pintype "passive"))
      (node (ref "JP1") (pin "9") (pinfunction "9_9") (pintype "passive"))
    )
    (net (code "51") (name "RFU_11") (class "Default")
      (node (ref "J1") (pin "11") (pinfunction "11_11") (pintype "passive"))
      (node (ref "J2") (pin "11") (pinfunction "11_11") (pintype "passive"))
      (node (ref "JP1") (pin "11") (pinfunction "11_11") (pintype "passive"))
    )
    (net (code "52") (name "RFU_13") (class "Default")
      (node (ref "J1") (pin "13") (pinfunction "13_13") (pintype "passive"))
      (node (ref "J2") (pin "13") (pinfunction "13_13") (pintype "passive"))
      (node (ref "JP1") (pin "13") (pinfunction "13_13") (pintype "passive"))
    )
    (net (code "53") (name "RFU_15") (class "Default")
      (node (ref "J1") (pin "15") (pinfunction "15_15") (pintype "passive"))
      (node (ref "J2") (pin "15") (pinfunction "15_15") (pintype "passive"))
      (node (ref "JP1") (pin "15") (pinfunction "15_15") (pintype "passive"))
    )
    (net (code "54") (name "RFU_17") (class "Default")
      (node (ref "J1") (pin "17") (pinfunction "17_17") (pintype "passive"))
      (node (ref "J2") (pin "17") (pinfunction "17_17") (pintype "passive"))
      (node (ref "JP1") (pin "17") (pinfunction "17_17") (pintype "passive"))
    )
    (net (code "55") (name "RFU_19") (class "Default")
      (node (ref "J1") (pin "19") (pinfunction "19_19") (pintype "passive"))
      (node (ref "J2") (pin "19") (pinfunction "19_19") (pintype "passive"))
      (node (ref "JP1") (pin "19") (pinfunction "19_19") (pintype "passive"))
    )
    (net (code "56") (name "RFU_21") (class "Default")
      (node (ref "J1") (pin "21") (pinfunction "21_21") (pintype "passive"))
      (node (ref "J2") (pin "21") (pinfunction "21_21") (pintype "passive"))
      (node (ref "JP1") (pin "21") (pinfunction "21_21") (pintype "passive"))
    )
    (net (code "57") (name "RFU_23") (class "Default")
      (node (ref "J1") (pin "23") (pinfunction "23_23") (pintype "passive"))
      (node (ref "J2") (pin "23") (pinfunction "23_23") (pintype "passive"))
      (node (ref "JP1") (pin "23") (pinfunction "23_23") (pintype "passive"))
    )
    (net (code "58") (name "RFU_25") (class "Default")
      (node (ref "J1") (pin "25") (pinfunction "25_25") (pintype "passive"))
      (node (ref "J2") (pin "25") (pinfunction "25_25") (pintype "passive"))
      (node (ref "JP1") (pin "25") (pinfunction "25_25") (pintype "passive"))
    )
    (net (code "59") (name "RFU_27") (class "Default")
      (node (ref "J1") (pin "27") (pinfunction "27_27") (pintype "passive"))
      (node (ref "J2") (pin "27") (pinfunction "27_27") (pintype "passive"))
      (node (ref "JP1") (pin "27") (pinfunction "27_27") (pintype "passive"))
    )
    (net (code "60") (name "RFU_29") (class "Default")
      (node (ref "J1") (pin "29") (pinfunction "29_29") (pintype "passive"))
      (node (ref "J2") (pin "29") (pinfunction "29_29") (pintype "passive"))
      (node (ref "JP1") (pin "29") (pinfunction "29_29") (pintype "passive"))
    )
    (net (code "61") (name "RFU_31") (class "Default")
      (node (ref "J1") (pin "31") (pinfunction "31_31") (pintype "passive"))
      (node (ref "J2") (pin "31") (pinfunction "31_31") (pintype "passive"))
      (node (ref "JP1") (pin "31") (pinfunction "31_31") (pintype "passive"))
    )
    (net (code "62") (name "RFU_33") (class "Default")
      (node (ref "J1") (pin "33") (pinfunction "33_33") (pintype "passive"))
      (node (ref "J2") (pin "33") (pinfunction "33_33") (pintype "passive"))
      (node (ref "JP1") (pin "33") (pinfunction "33_33") (pintype "passive"))
    )
    (net (code "63") (name "RFU_35") (class "Default")
      (node (ref "J1") (pin "35") (pinfunction "35_35") (pintype "passive"))
      (node (ref "J2") (pin "35") (pinfunction "35_35") (pintype "passive"))
      (node (ref "JP1") (pin "35") (pinfunction "35_35") (pintype "passive"))
    )
    (net (code "64") (name "RFU_37") (class "Default")
      (node (ref "J1") (pin "37") (pinfunction "37_37") (pintype "passive"))
      (node (ref "J2") (pin "37") (pinfunction "37_37") (pintype "passive"))
      (node (ref "JP1") (pin "37") (pinfunction "37_37") (pintype "passive"))
    )
    (net (code "65") (name "RS485_D_N") (class "Default")
      (node (ref "J1") (pin "28") (pinfunction "28_28") (pintype "passive"))
      (node (ref "J2") (pin "28") (pinfunction "28_28") (pintype "passive"))
      (node (ref "JP1") (pin "28") (pinfunction "28_28") (pintype "passive"))
    )
    (net (code "66") (name "RS485_D_P") (class "Default")
      (node (ref "J1") (pin "26") (pinfunction "26_26") (pintype "passive"))
      (node (ref "J2") (pin "26") (pinfunction "26_26") (pintype "passive"))
      (node (ref "JP1") (pin "26") (pinfunction "26_26") (pintype "passive"))
    )
    (net (code "67") (name "SPI_MISO") (class "Default")
      (node (ref "J1") (pin "12") (pinfunction "12_12") (pintype "passive"))
      (node (ref "J2") (pin "12") (pinfunction "12_12") (pintype "passive"))
      (node (ref "JP1") (pin "12") (pinfunction "12_12") (pintype "passive"))
      (node (ref "JP6") (pin "2") (pinfunction "2_2") (pintype "passive"))
    )
    (net (code "68") (name "SPI_MISO_R") (class "Default")
      (node (ref "JP10") (pin "1") (pinfunction "1_1") (pintype "passive"))
      (node (ref "JP6") (pin "1") (pinfunction "1_1") (pintype "passive"))
      (node (ref "JP9") (pin "9") (pinfunction "9_9") (pintype "passive"))
      (node (ref "U1") (pin "13") (pinfunction "PA08_13") (pintype "bidirectional"))
    )
    (net (code "69") (name "SPI_MOSI") (class "Default")
      (node (ref "J1") (pin "14") (pinfunction "14_14") (pintype "passive"))
      (node (ref "J2") (pin "14") (pinfunction "14_14") (pintype "passive"))
      (node (ref "JP1") (pin "14") (pinfunction "14_14") (pintype "passive"))
      (node (ref "JP7") (pin "2") (pinfunction "2_2") (pintype "passive"))
    )
    (net (code "70") (name "SPI_MOSI_R") (class "Default")
      (node (ref "JP10") (pin "2") (pinfunction "2_2") (pintype "passive"))
      (node (ref "JP7") (pin "1") (pinfunction "1_1") (pintype "passive"))
      (node (ref "JP9") (pin "11") (pinfunction "11_11") (pintype "passive"))
      (node (ref "U1") (pin "15") (pinfunction "PA10_15") (pintype "bidirectional"))
    )
    (net (code "71") (name "SPI_SCK") (class "Default")
      (node (ref "J1") (pin "16") (pinfunction "16_16") (pintype "passive"))
      (node (ref "J2") (pin "16") (pinfunction "16_16") (pintype "passive"))
      (node (ref "JP1") (pin "16") (pinfunction "16_16") (pintype "passive"))
      (node (ref "JP8") (pin "2") (pinfunction "2_2") (pintype "passive"))
    )
    (net (code "72") (name "SPI_SCK_R") (class "Default")
      (node (ref "JP10") (pin "3") (pinfunction "3_3") (pintype "passive"))
      (node (ref "JP8") (pin "1") (pinfunction "1_1") (pintype "passive"))
      (node (ref "JP9") (pin "12") (pinfunction "12_12") (pintype "passive"))
      (node (ref "U1") (pin "16") (pinfunction "PA11_16") (pintype "bidirectional"))
    )
    (net (code "73") (name "SWCLK") (class "Default")
      (node (ref "J6") (pin "4") (pinfunction "4_SWCLK_4") (pintype "passive"))
      (node (ref "R4") (pin "1") (pinfunction "1_1") (pintype "passive"))
      (node (ref "U1") (pin "45") (pinfunction "PA30/SWCLK_45") (pintype "bidirectional"))
    )
    (net (code "74") (name "SWDIO") (class "Default")
      (node (ref "J6") (pin "2") (pinfunction "2SWDIO_2") (pintype "passive"))
      (node (ref "U1") (pin "46") (pinfunction "PA31/SWDIO_46") (pintype "bidirectional"))
    )
    (net (code "75") (name "UART_RX") (class "Default")
      (node (ref "JP3") (pin "2") (pinfunction "2_2") (pintype "passive"))
      (node (ref "JP9") (pin "6") (pinfunction "6_6") (pintype "passive"))
      (node (ref "U1") (pin "10") (pinfunction "PA05_10") (pintype "bidirectional"))
    )
    (net (code "76") (name "UART_TX") (class "Default")
      (node (ref "JP3") (pin "1") (pinfunction "1_1") (pintype "passive"))
      (node (ref "JP9") (pin "5") (pinfunction "5_5") (pintype "passive"))
      (node (ref "U1") (pin "9") (pinfunction "PA04_9") (pintype "bidirectional"))
    )
    (net (code "77") (name "unconnected-(J6-6_SWO-Pad6)") (class "Default")
      (node (ref "J6") (pin "6") (pinfunction "6_SWO_6") (pintype "passive"))
    )
    (net (code "78") (name "unconnected-(J6-7_NC-Pad7)") (class "Default")
      (node (ref "J6") (pin "7") (pinfunction "7_NC_7") (pintype "passive"))
    )
    (net (code "79") (name "unconnected-(J6-8_NC-Pad8)") (class "Default")
      (node (ref "J6") (pin "8") (pinfunction "8_NC_8") (pintype "passive"))
    )
    (net (code "80") (name "unconnected-(U6-NC-Pad4)") (class "Default")
      (node (ref "U6") (pin "4") (pinfunction "NC_4") (pintype "no_connect"))
    )
  )
)
